# Display_PWR_CTRL.net
KiCad netlist of a schematic drawn in Altium Designer
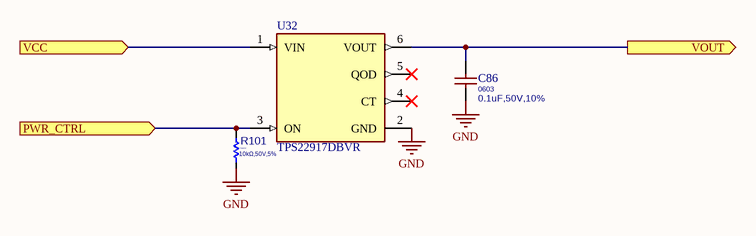
[diagram p0: Display_PWR_CTRL.SchDoc]

(export (version "E")
  (design (tool "Eeschema 10.0.6"))
  (components
    (comp (ref "C86")
      (value "0.1uF,50V,10%")
      (footprint "C0603")
      (description "CAP CER 0.1UF 50V X7R 0603")
      (fields
        (field (name "MANUFACTURER") "Murata Electronics")
        (field (name "MPN") "GCM188R71H104KA57J")
        (field (name "PACKAGE") "0603")
      )
      (libsource (lib "RCL") (part "GCM188R71H104KA57J"))
    )
    (comp (ref "R101")
      (value "10kΩ,50V,5%")
      (footprint "R0402")
      (description "62.5mW Thick Film Resistors 50V ±100ppm/℃ ±5% 10kΩ 0402 Chip Resistor - Surface Mount ROHS")
      (fields
        (field (name "MANUFACTURER") "YAGEO")
        (field (name "MPN") "RC0402JR-0710KL")
        (field (name "PACKAGE") "0402")
      )
      (libsource (lib "RCL") (part "RC0402JR-0710KL"))
    )
    (comp (ref "U32")
      (value "TPS22917DBVR")
      (footprint "SOT95P280X145-6N")
      (description "5.5-V, 2-A, 80-mÎ© , 10-nA leakage load switch adj. rise time and adj output discharge")
      (fields (field (name "MF") "Texas Instruments"))
      (libsource (lib "IC") (part "TPS22917DBVR"))
    )
  )
  (nets
    (net (code "1") (name "/PWR_CTRL") (class "Default")
      (node (ref "R101") (pin "2") (pinfunction "2_2") (pintype "passive"))
      (node (ref "U32") (pin "3") (pinfunction "ON_3") (pintype "input"))
    )
    (net (code "2") (name "/VCC") (class "Default")
      (node (ref "U32") (pin "1") (pinfunction "VIN_1") (pintype "input"))
    )
    (net (code "3") (name "/VOUT") (class "Default")
      (node (ref "C86") (pin "2") (pinfunction "2_2") (pintype "passive"))
      (node (ref "U32") (pin "6") (pinfunction "VOUT_6") (pintype "output"))
    )
    (net (code "4") (name "GND") (class "Default")
      (node (ref "C86") (pin "1") (pinfunction "1_1") (pintype "passive"))
      (node (ref "R101") (pin "1") (pinfunction "1_1") (pintype "passive"))
      (node (ref "U32") (pin "2") (pinfunction "GND_2") (pintype "power_in"))
    )
    (net (code "5") (name "unconnected-(U32-CT-Pad4)") (class "Default")
      (node (ref "U32") (pin "4") (pinfunction "CT_4") (pintype "output+no_connect"))
    )
    (net (code "6") (name "unconnected-(U32-QOD-Pad5)") (class "Default")
      (node (ref "U32") (pin "5") (pinfunction "QOD_5") (pintype "output+no_connect"))
    )
  )
)
